# BMS.net
KiCad netlist of a schematic drawn in Altium Designer
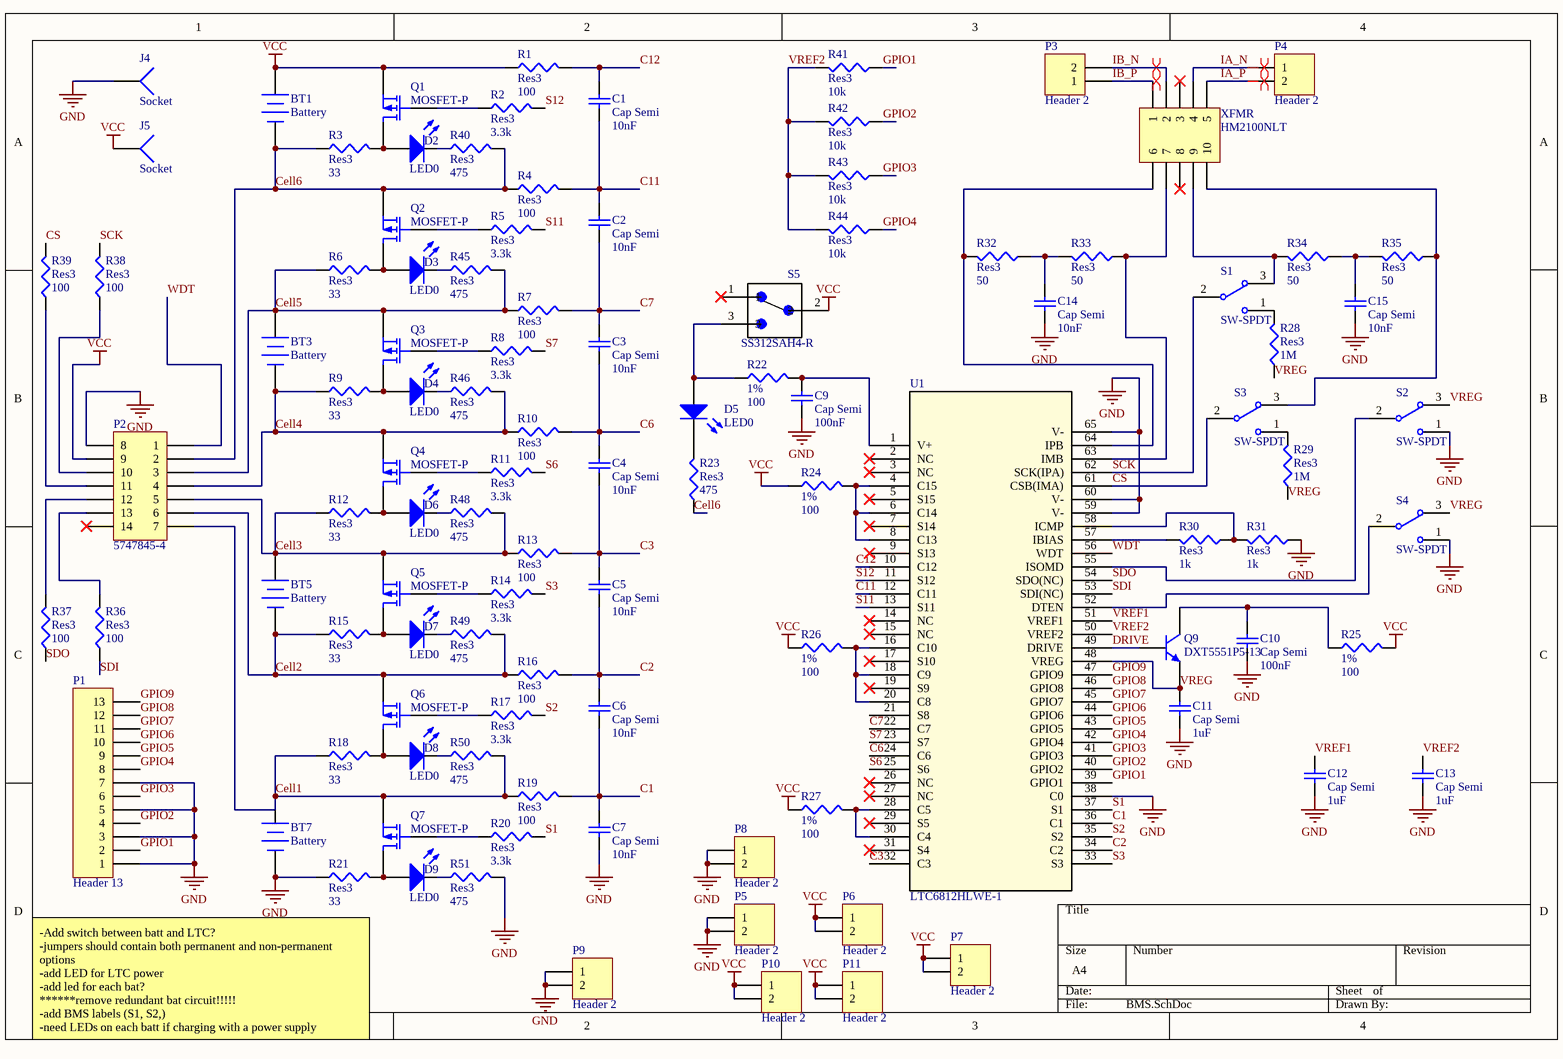
[diagram p0: BMS.SchDoc]

(export (version "E")
  (design (tool "Eeschema 10.0.6"))
  (components
    (comp (ref "BT1")
      (value "Battery")
      (footprint "18650 SMD:PCBComponent_1")
      (description "Multicell Battery")
      (fields (field (name "PUBLISHER") "Altium Limited"))
      (libsource (lib "Miscellaneous Devices") (part "Battery"))
    )
    (comp (ref "BT3")
      (value "Battery")
      (footprint "18650 SMD:PCBComponent_1")
      (description "Multicell Battery")
      (fields (field (name "PUBLISHER") "Altium Limited"))
      (libsource (lib "Miscellaneous Devices") (part "Battery"))
    )
    (comp (ref "BT5")
      (value "Battery")
      (footprint "18650 SMD:PCBComponent_1")
      (description "Multicell Battery")
      (fields (field (name "PUBLISHER") "Altium Limited"))
      (libsource (lib "Miscellaneous Devices") (part "Battery"))
    )
    (comp (ref "BT7")
      (value "Battery")
      (footprint "18650 SMD:PCBComponent_1")
      (description "Multicell Battery")
      (fields (field (name "PUBLISHER") "Altium Limited"))
      (libsource (lib "Miscellaneous Devices") (part "Battery"))
    )
    (comp (ref "C1")
      (value "Cap Semi")
      (footprint "1608[0603]")
      (description "Capacitor (Semiconductor SIM Model)")
      (fields (field (name "ALTIUM_VALUE") "10nF") (field (name "PUBLISHER") "Altium Limited"))
      (libsource (lib "Miscellaneous Devices") (part "Cap Semi"))
    )
    (comp (ref "C2")
      (value "Cap Semi")
      (footprint "1608[0603]")
      (description "Capacitor (Semiconductor SIM Model)")
      (fields (field (name "ALTIUM_VALUE") "10nF") (field (name "PUBLISHER") "Altium Limited"))
      (libsource (lib "Miscellaneous Devices") (part "Cap Semi"))
    )
    (comp (ref "C3")
      (value "Cap Semi")
      (footprint "1608[0603]")
      (description "Capacitor (Semiconductor SIM Model)")
      (fields (field (name "ALTIUM_VALUE") "10nF") (field (name "PUBLISHER") "Altium Limited"))
      (libsource (lib "Miscellaneous Devices") (part "Cap Semi"))
    )
    (comp (ref "C4")
      (value "Cap Semi")
      (footprint "1608[0603]")
      (description "Capacitor (Semiconductor SIM Model)")
      (fields (field (name "ALTIUM_VALUE") "10nF") (field (name "PUBLISHER") "Altium Limited"))
      (libsource (lib "Miscellaneous Devices") (part "Cap Semi"))
    )
    (comp (ref "C5")
      (value "Cap Semi")
      (footprint "1608[0603]")
      (description "Capacitor (Semiconductor SIM Model)")
      (fields (field (name "ALTIUM_VALUE") "10nF") (field (name "PUBLISHER") "Altium Limited"))
      (libsource (lib "Miscellaneous Devices") (part "Cap Semi"))
    )
    (comp (ref "C6")
      (value "Cap Semi")
      (footprint "1608[0603]")
      (description "Capacitor (Semiconductor SIM Model)")
      (fields (field (name "ALTIUM_VALUE") "10nF") (field (name "PUBLISHER") "Altium Limited"))
      (libsource (lib "Miscellaneous Devices") (part "Cap Semi"))
    )
    (comp (ref "C7")
      (value "Cap Semi")
      (footprint "1608[0603]")
      (description "Capacitor (Semiconductor SIM Model)")
      (fields (field (name "ALTIUM_VALUE") "10nF") (field (name "PUBLISHER") "Altium Limited"))
      (libsource (lib "Miscellaneous Devices") (part "Cap Semi"))
    )
    (comp (ref "C9")
      (value "Cap Semi")
      (footprint "6-0805_N")
      (description "Capacitor (Semiconductor SIM Model)")
      (fields (field (name "ALTIUM_VALUE") "100nF") (field (name "PUBLISHER") "Altium Limited"))
      (libsource (lib "Miscellaneous Devices") (part "Cap Semi"))
    )
    (comp (ref "C10")
      (value "Cap Semi")
      (footprint "6-0805_N")
      (description "Capacitor (Semiconductor SIM Model)")
      (fields (field (name "ALTIUM_VALUE") "100nF") (field (name "PUBLISHER") "Altium Limited"))
      (libsource (lib "Miscellaneous Devices") (part "Cap Semi"))
    )
    (comp (ref "C11")
      (value "Cap Semi")
      (footprint "6-0805_N")
      (description "Capacitor (Semiconductor SIM Model)")
      (fields (field (name "ALTIUM_VALUE") "1uF") (field (name "PUBLISHER") "Altium Limited"))
      (libsource (lib "Miscellaneous Devices") (part "Cap Semi"))
    )
    (comp (ref "C12")
      (value "Cap Semi")
      (footprint "6-0805_N")
      (description "Capacitor (Semiconductor SIM Model)")
      (fields (field (name "ALTIUM_VALUE") "1uF") (field (name "PUBLISHER") "Altium Limited"))
      (libsource (lib "Miscellaneous Devices") (part "Cap Semi"))
    )
    (comp (ref "C13")
      (value "Cap Semi")
      (footprint "6-0805_N")
      (description "Capacitor (Semiconductor SIM Model)")
      (fields (field (name "ALTIUM_VALUE") "1uF") (field (name "PUBLISHER") "Altium Limited"))
      (libsource (lib "Miscellaneous Devices") (part "Cap Semi"))
    )
    (comp (ref "C14")
      (value "Cap Semi")
      (footprint "1608[0603]")
      (description "Capacitor (Semiconductor SIM Model)")
      (fields (field (name "ALTIUM_VALUE") "10nF") (field (name "PUBLISHER") "Altium Limited"))
      (libsource (lib "Miscellaneous Devices") (part "Cap Semi"))
    )
    (comp (ref "C15")
      (value "Cap Semi")
      (footprint "1608[0603]")
      (description "Capacitor (Semiconductor SIM Model)")
      (fields (field (name "ALTIUM_VALUE") "10nF") (field (name "PUBLISHER") "Altium Limited"))
      (libsource (lib "Miscellaneous Devices") (part "Cap Semi"))
    )
    (comp (ref "D2")
      (value "LED0")
      (footprint "J1-0603")
      (description "Typical INFRARED GaAs LED")
      (fields (field (name "PUBLISHER") "Altium Limited"))
      (libsource (lib "Miscellaneous Devices") (part "LED0"))
    )
    (comp (ref "D3")
      (value "LED0")
      (footprint "J1-0603")
      (description "Typical INFRARED GaAs LED")
      (fields (field (name "PUBLISHER") "Altium Limited"))
      (libsource (lib "Miscellaneous Devices") (part "LED0"))
    )
    (comp (ref "D4")
      (value "LED0")
      (footprint "J1-0603")
      (description "Typical INFRARED GaAs LED")
      (fields (field (name "PUBLISHER") "Altium Limited"))
      (libsource (lib "Miscellaneous Devices") (part "LED0"))
    )
    (comp (ref "D5")
      (value "LED0")
      (footprint "J1-0603")
      (description "Typical INFRARED GaAs LED")
      (fields (field (name "PUBLISHER") "Altium Limited"))
      (libsource (lib "Miscellaneous Devices") (part "LED0"))
    )
    (comp (ref "D6")
      (value "LED0")
      (footprint "J1-0603")
      (description "Typical INFRARED GaAs LED")
      (fields (field (name "PUBLISHER") "Altium Limited"))
      (libsource (lib "Miscellaneous Devices") (part "LED0"))
    )
    (comp (ref "D7")
      (value "LED0")
      (footprint "J1-0603")
      (description "Typical INFRARED GaAs LED")
      (fields (field (name "PUBLISHER") "Altium Limited"))
      (libsource (lib "Miscellaneous Devices") (part "LED0"))
    )
    (comp (ref "D8")
      (value "LED0")
      (footprint "J1-0603")
      (description "Typical INFRARED GaAs LED")
      (fields (field (name "PUBLISHER") "Altium Limited"))
      (libsource (lib "Miscellaneous Devices") (part "LED0"))
    )
    (comp (ref "D9")
      (value "LED0")
      (footprint "J1-0603")
      (description "Typical INFRARED GaAs LED")
      (fields (field (name "PUBLISHER") "Altium Limited"))
      (libsource (lib "Miscellaneous Devices") (part "LED0"))
    )
    (comp (ref "J4")
      (value "Socket")
      (footprint "SMD Power Pad:PCBComponent_1")
      (fields (field (name "PUBLISHER") "Altium Limited"))
      (libsource (lib "Miscellaneous Connectors") (part "Socket"))
    )
    (comp (ref "J5")
      (value "Socket")
      (footprint "SMD Power Pad:PCBComponent_1")
      (fields (field (name "PUBLISHER") "Altium Limited"))
      (libsource (lib "Miscellaneous Connectors") (part "Socket"))
    )
    (comp (ref "P1")
      (value "Header 13")
      (footprint "SMD Finger Pads:PCBComponent_1")
      (description "Header, 13-Pin")
      (fields (field (name "PUBLISHER") "Altium Limited"))
      (libsource (lib "Miscellaneous Connectors") (part "Header 13"))
    )
    (comp (ref "P2")
      (value "5747845-4")
      (footprint "*5747845-4")
      (description "Header, 7-Pin, Dual row")
      (fields (field (name "PUBLISHER") "Altium Limited"))
      (libsource (lib "Miscellaneous Connectors") (part "Header 7X2A"))
    )
    (comp (ref "P3")
      (value "Header 2")
      (footprint "Molex Connectors:WM4900-ND")
      (description "Header, 2-Pin")
      (fields (field (name "PUBLISHER") "Altium Limited"))
      (libsource (lib "") (part "Header 2_1"))
    )
    (comp (ref "P4")
      (value "Header 2")
      (footprint "Molex Connectors:WM4900-ND")
      (description "Header, 2-Pin")
      (fields (field (name "PUBLISHER") "Altium Limited"))
      (libsource (lib "Miscellaneous Connectors") (part "Header 2"))
    )
    (comp (ref "P5")
      (value "Header 2")
      (footprint "5104:PCBComponent_1")
      (description "Header, 2-Pin")
      (fields (field (name "PUBLISHER") "Altium Limited"))
      (libsource (lib "Miscellaneous Connectors") (part "Header 2"))
    )
    (comp (ref "P6")
      (value "Header 2")
      (footprint "5104:PCBComponent_1")
      (description "Header, 2-Pin")
      (fields (field (name "PUBLISHER") "Altium Limited"))
      (libsource (lib "Miscellaneous Connectors") (part "Header 2"))
    )
    (comp (ref "P7")
      (value "Header 2")
      (footprint "5104:PCBComponent_1")
      (description "Header, 2-Pin")
      (fields (field (name "PUBLISHER") "Altium Limited"))
      (libsource (lib "Miscellaneous Connectors") (part "Header 2"))
    )
    (comp (ref "P8")
      (value "Header 2")
      (footprint "5104:PCBComponent_1")
      (description "Header, 2-Pin")
      (fields (field (name "PUBLISHER") "Altium Limited"))
      (libsource (lib "Miscellaneous Connectors") (part "Header 2"))
    )
    (comp (ref "P9")
      (value "Header 2")
      (footprint "5104:PCBComponent_1")
      (description "Header, 2-Pin")
      (fields (field (name "PUBLISHER") "Altium Limited"))
      (libsource (lib "Miscellaneous Connectors") (part "Header 2"))
    )
    (comp (ref "P10")
      (value "Header 2")
      (footprint "5104:PCBComponent_1")
      (description "Header, 2-Pin")
      (fields (field (name "PUBLISHER") "Altium Limited"))
      (libsource (lib "Miscellaneous Connectors") (part "Header 2"))
    )
    (comp (ref "P11")
      (value "Header 2")
      (footprint "5104:PCBComponent_1")
      (description "Header, 2-Pin")
      (fields (field (name "PUBLISHER") "Altium Limited"))
      (libsource (lib "Miscellaneous Connectors") (part "Header 2"))
    )
    (comp (ref "Q1")
      (value "MOSFET-P")
      (footprint "SOT95P245X110-3N")
      (description "P-Channel MOSFET")
      (fields (field (name "PUBLISHER") "Altium Limited"))
      (libsource (lib "Miscellaneous Devices") (part "MOSFET-P"))
    )
    (comp (ref "Q2")
      (value "MOSFET-P")
      (footprint "SOT95P245X110-3N")
      (description "P-Channel MOSFET")
      (fields (field (name "PUBLISHER") "Altium Limited"))
      (libsource (lib "Miscellaneous Devices") (part "MOSFET-P"))
    )
    (comp (ref "Q3")
      (value "MOSFET-P")
      (footprint "SOT95P245X110-3N")
      (description "P-Channel MOSFET")
      (fields (field (name "PUBLISHER") "Altium Limited"))
      (libsource (lib "Miscellaneous Devices") (part "MOSFET-P"))
    )
    (comp (ref "Q4")
      (value "MOSFET-P")
      (footprint "SOT95P245X110-3N")
      (description "P-Channel MOSFET")
      (fields (field (name "PUBLISHER") "Altium Limited"))
      (libsource (lib "Miscellaneous Devices") (part "MOSFET-P"))
    )
    (comp (ref "Q5")
      (value "MOSFET-P")
      (footprint "SOT95P245X110-3N")
      (description "P-Channel MOSFET")
      (fields (field (name "PUBLISHER") "Altium Limited"))
      (libsource (lib "Miscellaneous Devices") (part "MOSFET-P"))
    )
    (comp (ref "Q6")
      (value "MOSFET-P")
      (footprint "SOT95P245X110-3N")
      (description "P-Channel MOSFET")
      (fields (field (name "PUBLISHER") "Altium Limited"))
      (libsource (lib "Miscellaneous Devices") (part "MOSFET-P"))
    )
    (comp (ref "Q7")
      (value "MOSFET-P")
      (footprint "SOT95P245X110-3N")
      (description "P-Channel MOSFET")
      (fields (field (name "PUBLISHER") "Altium Limited"))
      (libsource (lib "Miscellaneous Devices") (part "MOSFET-P"))
    )
    (comp (ref "Q9")
      (value "DXT5551P5-13")
      (footprint "DXT5551P5-13")
      (description "NPN General Purpose Amplifier")
      (fields (field (name "PUBLISHER") "Altium Limited"))
      (libsource (lib "Miscellaneous Devices") (part "2N3904"))
    )
    (comp (ref "R1")
      (value "Res3")
      (footprint "J1-0603")
      (description "Resistor")
      (fields (field (name "ALTIUM_VALUE") "100") (field (name "PUBLISHER") "Altium Limited"))
      (libsource (lib "Miscellaneous Devices") (part "Res3"))
    )
    (comp (ref "R2")
      (value "Res3")
      (footprint "J1-0603")
      (description "Resistor")
      (fields (field (name "ALTIUM_VALUE") "3.3k") (field (name "PUBLISHER") "Altium Limited"))
      (libsource (lib "Miscellaneous Devices") (part "Res3"))
    )
    (comp (ref "R3")
      (value "Res3")
      (footprint "12Z-2010")
      (description "Resistor")
      (fields (field (name "ALTIUM_VALUE") "33") (field (name "PUBLISHER") "Altium Limited"))
      (libsource (lib "Miscellaneous Devices") (part "Res3"))
    )
    (comp (ref "R4")
      (value "Res3")
      (footprint "J1-0603")
      (description "Resistor")
      (fields (field (name "ALTIUM_VALUE") "100") (field (name "PUBLISHER") "Altium Limited"))
      (libsource (lib "Miscellaneous Devices") (part "Res3"))
    )
    (comp (ref "R5")
      (value "Res3")
      (footprint "J1-0603")
      (description "Resistor")
      (fields (field (name "ALTIUM_VALUE") "3.3k") (field (name "PUBLISHER") "Altium Limited"))
      (libsource (lib "Miscellaneous Devices") (part "Res3"))
    )
    (comp (ref "R6")
      (value "Res3")
      (footprint "12Z-2010")
      (description "Resistor")
      (fields (field (name "ALTIUM_VALUE") "33") (field (name "PUBLISHER") "Altium Limited"))
      (libsource (lib "Miscellaneous Devices") (part "Res3"))
    )
    (comp (ref "R7")
      (value "Res3")
      (footprint "J1-0603")
      (description "Resistor")
      (fields (field (name "ALTIUM_VALUE") "100") (field (name "PUBLISHER") "Altium Limited"))
      (libsource (lib "Miscellaneous Devices") (part "Res3"))
    )
    (comp (ref "R8")
      (value "Res3")
      (footprint "J1-0603")
      (description "Resistor")
      (fields (field (name "ALTIUM_VALUE") "3.3k") (field (name "PUBLISHER") "Altium Limited"))
      (libsource (lib "Miscellaneous Devices") (part "Res3"))
    )
    (comp (ref "R9")
      (value "Res3")
      (footprint "12Z-2010")
      (description "Resistor")
      (fields (field (name "ALTIUM_VALUE") "33") (field (name "PUBLISHER") "Altium Limited"))
      (libsource (lib "Miscellaneous Devices") (part "Res3"))
    )
    (comp (ref "R10")
      (value "Res3")
      (footprint "J1-0603")
      (description "Resistor")
      (fields (field (name "ALTIUM_VALUE") "100") (field (name "PUBLISHER") "Altium Limited"))
      (libsource (lib "Miscellaneous Devices") (part "Res3"))
    )
    (comp (ref "R11")
      (value "Res3")
      (footprint "J1-0603")
      (description "Resistor")
      (fields (field (name "ALTIUM_VALUE") "3.3k") (field (name "PUBLISHER") "Altium Limited"))
      (libsource (lib "Miscellaneous Devices") (part "Res3"))
    )
    (comp (ref "R12")
      (value "Res3")
      (footprint "12Z-2010")
      (description "Resistor")
      (fields (field (name "ALTIUM_VALUE") "33") (field (name "PUBLISHER") "Altium Limited"))
      (libsource (lib "Miscellaneous Devices") (part "Res3"))
    )
    (comp (ref "R13")
      (value "Res3")
      (footprint "J1-0603")
      (description "Resistor")
      (fields (field (name "ALTIUM_VALUE") "100") (field (name "PUBLISHER") "Altium Limited"))
      (libsource (lib "Miscellaneous Devices") (part "Res3"))
    )
    (comp (ref "R14")
      (value "Res3")
      (footprint "J1-0603")
      (description "Resistor")
      (fields (field (name "ALTIUM_VALUE") "3.3k") (field (name "PUBLISHER") "Altium Limited"))
      (libsource (lib "Miscellaneous Devices") (part "Res3"))
    )
    (comp (ref "R15")
      (value "Res3")
      (footprint "12Z-2010")
      (description "Resistor")
      (fields (field (name "ALTIUM_VALUE") "33") (field (name "PUBLISHER") "Altium Limited"))
      (libsource (lib "Miscellaneous Devices") (part "Res3"))
    )
    (comp (ref "R16")
      (value "Res3")
      (footprint "J1-0603")
      (description "Resistor")
      (fields (field (name "ALTIUM_VALUE") "100") (field (name "PUBLISHER") "Altium Limited"))
      (libsource (lib "Miscellaneous Devices") (part "Res3"))
    )
    (comp (ref "R17")
      (value "Res3")
      (footprint "J1-0603")
      (description "Resistor")
      (fields (field (name "ALTIUM_VALUE") "3.3k") (field (name "PUBLISHER") "Altium Limited"))
      (libsource (lib "Miscellaneous Devices") (part "Res3"))
    )
    (comp (ref "R18")
      (value "Res3")
      (footprint "12Z-2010")
      (description "Resistor")
      (fields (field (name "ALTIUM_VALUE") "33") (field (name "PUBLISHER") "Altium Limited"))
      (libsource (lib "Miscellaneous Devices") (part "Res3"))
    )
    (comp (ref "R19")
      (value "Res3")
      (footprint "J1-0603")
      (description "Resistor")
      (fields (field (name "ALTIUM_VALUE") "100") (field (name "PUBLISHER") "Altium Limited"))
      (libsource (lib "Miscellaneous Devices") (part "Res3"))
    )
    (comp (ref "R20")
      (value "Res3")
      (footprint "J1-0603")
      (description "Resistor")
      (fields (field (name "ALTIUM_VALUE") "3.3k") (field (name "PUBLISHER") "Altium Limited"))
      (libsource (lib "Miscellaneous Devices") (part "Res3"))
    )
    (comp (ref "R21")
      (value "Res3")
      (footprint "12Z-2010")
      (description "Resistor")
      (fields (field (name "ALTIUM_VALUE") "33") (field (name "PUBLISHER") "Altium Limited"))
      (libsource (lib "Miscellaneous Devices") (part "Res3"))
    )
    (comp (ref "R22")
      (value "1%")
      (footprint "J1-0603")
      (description "Resistor")
      (fields (field (name "ALTIUM_VALUE") "100") (field (name "PUBLISHER") "Altium Limited"))
      (libsource (lib "Miscellaneous Devices") (part "Res3"))
    )
    (comp (ref "R23")
      (value "Res3")
      (footprint "J1-0603")
      (description "Resistor")
      (fields (field (name "ALTIUM_VALUE") "475") (field (name "PUBLISHER") "Altium Limited"))
      (libsource (lib "Miscellaneous Devices") (part "Res3"))
    )
    (comp (ref "R24")
      (value "1%")
      (footprint "J1-0603")
      (description "Resistor")
      (fields (field (name "ALTIUM_VALUE") "100") (field (name "PUBLISHER") "Altium Limited"))
      (libsource (lib "Miscellaneous Devices") (part "Res3"))
    )
    (comp (ref "R25")
      (value "1%")
      (footprint "J1-0603")
      (description "Resistor")
      (fields (field (name "ALTIUM_VALUE") "100") (field (name "PUBLISHER") "Altium Limited"))
      (libsource (lib "Miscellaneous Devices") (part "Res3"))
    )
    (comp (ref "R26")
      (value "1%")
      (footprint "J1-0603")
      (description "Resistor")
      (fields (field (name "ALTIUM_VALUE") "100") (field (name "PUBLISHER") "Altium Limited"))
      (libsource (lib "Miscellaneous Devices") (part "Res3"))
    )
    (comp (ref "R27")
      (value "1%")
      (footprint "J1-0603")
      (description "Resistor")
      (fields (field (name "ALTIUM_VALUE") "100") (field (name "PUBLISHER") "Altium Limited"))
      (libsource (lib "Miscellaneous Devices") (part "Res3"))
    )
    (comp (ref "R28")
      (value "Res3")
      (footprint "J1-0603")
      (description "Resistor")
      (fields (field (name "ALTIUM_VALUE") "1M") (field (name "PUBLISHER") "Altium Limited"))
      (libsource (lib "Miscellaneous Devices") (part "Res3"))
    )
    (comp (ref "R29")
      (value "Res3")
      (footprint "J1-0603")
      (description "Resistor")
      (fields (field (name "ALTIUM_VALUE") "1M") (field (name "PUBLISHER") "Altium Limited"))
      (libsource (lib "Miscellaneous Devices") (part "Res3"))
    )
    (comp (ref "R30")
      (value "Res3")
      (footprint "J1-0603")
      (description "Resistor")
      (fields (field (name "ALTIUM_VALUE") "1k") (field (name "PUBLISHER") "Altium Limited"))
      (libsource (lib "Miscellaneous Devices") (part "Res3"))
    )
    (comp (ref "R31")
      (value "Res3")
      (footprint "J1-0603")
      (description "Resistor")
      (fields (field (name "ALTIUM_VALUE") "1k") (field (name "PUBLISHER") "Altium Limited"))
      (libsource (lib "Miscellaneous Devices") (part "Res3"))
    )
    (comp (ref "R32")
      (value "Res3")
      (footprint "J1-0603")
      (description "Resistor")
      (fields (field (name "ALTIUM_VALUE") "50") (field (name "PUBLISHER") "Altium Limited"))
      (libsource (lib "Miscellaneous Devices") (part "Res3"))
    )
    (comp (ref "R33")
      (value "Res3")
      (footprint "J1-0603")
      (description "Resistor")
      (fields (field (name "ALTIUM_VALUE") "50") (field (name "PUBLISHER") "Altium Limited"))
      (libsource (lib "Miscellaneous Devices") (part "Res3"))
    )
    (comp (ref "R34")
      (value "Res3")
      (footprint "J1-0603")
      (description "Resistor")
      (fields (field (name "ALTIUM_VALUE") "50") (field (name "PUBLISHER") "Altium Limited"))
      (libsource (lib "Miscellaneous Devices") (part "Res3"))
    )
    (comp (ref "R35")
      (value "Res3")
      (footprint "J1-0603")
      (description "Resistor")
      (fields (field (name "ALTIUM_VALUE") "50") (field (name "PUBLISHER") "Altium Limited"))
      (libsource (lib "Miscellaneous Devices") (part "Res3"))
    )
    (comp (ref "R36")
      (value "Res3")
      (footprint "J1-0603")
      (description "Resistor")
      (fields (field (name "ALTIUM_VALUE") "100") (field (name "PUBLISHER") "Altium Limited"))
      (libsource (lib "Miscellaneous Devices") (part "Res3"))
    )
    (comp (ref "R37")
      (value "Res3")
      (footprint "J1-0603")
      (description "Resistor")
      (fields (field (name "ALTIUM_VALUE") "100") (field (name "PUBLISHER") "Altium Limited"))
      (libsource (lib "Miscellaneous Devices") (part "Res3"))
    )
    (comp (ref "R38")
      (value "Res3")
      (footprint "J1-0603")
      (description "Resistor")
      (fields (field (name "ALTIUM_VALUE") "100") (field (name "PUBLISHER") "Altium Limited"))
      (libsource (lib "Miscellaneous Devices") (part "Res3"))
    )
    (comp (ref "R39")
      (value "Res3")
      (footprint "J1-0603")
      (description "Resistor")
      (fields (field (name "ALTIUM_VALUE") "100") (field (name "PUBLISHER") "Altium Limited"))
      (libsource (lib "Miscellaneous Devices") (part "Res3"))
    )
    (comp (ref "R40")
      (value "Res3")
      (footprint "J1-0603")
      (description "Resistor")
      (fields (field (name "ALTIUM_VALUE") "475") (field (name "PUBLISHER") "Altium Limited"))
      (libsource (lib "Miscellaneous Devices") (part "Res3"))
    )
    (comp (ref "R41")
      (value "Res3")
      (footprint "J1-0603")
      (description "Resistor")
      (fields (field (name "ALTIUM_VALUE") "10k") (field (name "PUBLISHER") "Altium Limited"))
      (libsource (lib "Miscellaneous Devices") (part "Res3"))
    )
    (comp (ref "R42")
      (value "Res3")
      (footprint "J1-0603")
      (description "Resistor")
      (fields (field (name "ALTIUM_VALUE") "10k") (field (name "PUBLISHER") "Altium Limited"))
      (libsource (lib "Miscellaneous Devices") (part "Res3"))
    )
    (comp (ref "R43")
      (value "Res3")
      (footprint "J1-0603")
      (description "Resistor")
      (fields (field (name "ALTIUM_VALUE") "10k") (field (name "PUBLISHER") "Altium Limited"))
      (libsource (lib "Miscellaneous Devices") (part "Res3"))
    )
    (comp (ref "R44")
      (value "Res3")
      (footprint "J1-0603")
      (description "Resistor")
      (fields (field (name "ALTIUM_VALUE") "10k") (field (name "PUBLISHER") "Altium Limited"))
      (libsource (lib "Miscellaneous Devices") (part "Res3"))
    )
    (comp (ref "R45")
      (value "Res3")
      (footprint "J1-0603")
      (description "Resistor")
      (fields (field (name "ALTIUM_VALUE") "475") (field (name "PUBLISHER") "Altium Limited"))
      (libsource (lib "Miscellaneous Devices") (part "Res3"))
    )
    (comp (ref "R46")
      (value "Res3")
      (footprint "J1-0603")
      (description "Resistor")
      (fields (field (name "ALTIUM_VALUE") "475") (field (name "PUBLISHER") "Altium Limited"))
      (libsource (lib "Miscellaneous Devices") (part "Res3"))
    )
    (comp (ref "R48")
      (value "Res3")
      (footprint "J1-0603")
      (description "Resistor")
      (fields (field (name "ALTIUM_VALUE") "475") (field (name "PUBLISHER") "Altium Limited"))
      (libsource (lib "Miscellaneous Devices") (part "Res3"))
    )
    (comp (ref "R49")
      (value "Res3")
      (footprint "J1-0603")
      (description "Resistor")
      (fields (field (name "ALTIUM_VALUE") "475") (field (name "PUBLISHER") "Altium Limited"))
      (libsource (lib "Miscellaneous Devices") (part "Res3"))
    )
    (comp (ref "R50")
      (value "Res3")
      (footprint "J1-0603")
      (description "Resistor")
      (fields (field (name "ALTIUM_VALUE") "475") (field (name "PUBLISHER") "Altium Limited"))
      (libsource (lib "Miscellaneous Devices") (part "Res3"))
    )
    (comp (ref "R51")
      (value "Res3")
      (footprint "J1-0603")
      (description "Resistor")
      (fields (field (name "ALTIUM_VALUE") "475") (field (name "PUBLISHER") "Altium Limited"))
      (libsource (lib "Miscellaneous Devices") (part "Res3"))
    )
    (comp (ref "S1")
      (value "SW-SPDT")
      (footprint "*TSM-103-01-L-SV")
      (description "SPDT Subminiature Toggle Switch, Right Angle Mounting, Vertical Actuation")
      (fields (field (name "PUBLISHER") "Altium Limited"))
      (libsource (lib "Miscellaneous Devices") (part "SW-SPDT"))
    )
    (comp (ref "S2")
      (value "SW-SPDT")
      (footprint "*TSM-103-01-L-SV")
      (description "SPDT Subminiature Toggle Switch, Right Angle Mounting, Vertical Actuation")
      (fields (field (name "PUBLISHER") "Altium Limited"))
      (libsource (lib "Miscellaneous Devices") (part "SW-SPDT"))
    )
    (comp (ref "S3")
      (value "SW-SPDT")
      (footprint "*TSM-103-01-L-SV")
      (description "SPDT Subminiature Toggle Switch, Right Angle Mounting, Vertical Actuation")
      (fields (field (name "PUBLISHER") "Altium Limited"))
      (libsource (lib "Miscellaneous Devices") (part "SW-SPDT"))
    )
    (comp (ref "S4")
      (value "SW-SPDT")
      (footprint "*TSM-103-01-L-SV")
      (description "SPDT Subminiature Toggle Switch, Right Angle Mounting, Vertical Actuation")
      (fields (field (name "PUBLISHER") "Altium Limited"))
      (libsource (lib "Miscellaneous Devices") (part "SW-SPDT"))
    )
    (comp (ref "S5")
      (value "SS312SAH4-R")
      (footprint "*SW_SS312SAH4-R")
      (description "Switch Slide ON None ON SPDT Side Slide 0.1A 28VAC 28VDC 0.4VA 10000Cycles Gull Wing SMD T/R")
      (fields (field (name "MF") "NKK Switches"))
      (libsource (lib "SS312SAH4-R") (part "SS312SAH4-R"))
    )
    (comp (ref "U1")
      (value "LTC6812HLWE-1")
      (footprint "LQFP64_LWE_A - duplicate")
      (description "No Description Available")
      (fields (field (name "COPYRIGHT") "Copyright (C) 2018 Accelerated Designs. All rights reserved"))
      (libsource (lib "LTC6812") (part "LTC6812HLWE-1"))
    )
    (comp (ref "XFMR")
      (value "HM2100NLT")
      (footprint "HM2100NLT")
      (description "Header, 5-Pin, Dual row")
      (fields (field (name "PUBLISHER") "Altium Limited"))
      (libsource (lib "Miscellaneous Connectors") (part "Header 5X2A"))
    )
  )
  (nets
    (net (code "1") (name "/C1") (class "Default")
      (node (ref "C6") (pin "1") (pinfunction "1_1") (pintype "passive"))
      (node (ref "C7") (pin "2") (pinfunction "2_2") (pintype "passive"))
      (node (ref "R19") (pin "2") (pinfunction "2_2") (pintype "passive"))
      (node (ref "U1") (pin "36") (pinfunction "C1_36") (pintype "passive"))
    )
    (net (code "2") (name "/C2") (class "Default")
      (node (ref "C5") (pin "1") (pinfunction "1_1") (pintype "passive"))
      (node (ref "C6") (pin "2") (pinfunction "2_2") (pintype "passive"))
      (node (ref "R16") (pin "2") (pinfunction "2_2") (pintype "passive"))
      (node (ref "U1") (pin "34") (pinfunction "C2_34") (pintype "passive"))
    )
    (net (code "3") (name "/C3") (class "Default")
      (node (ref "C4") (pin "1") (pinfunction "1_1") (pintype "passive"))
      (node (ref "C5") (pin "2") (pinfunction "2_2") (pintype "passive"))
      (node (ref "R13") (pin "2") (pinfunction "2_2") (pintype "passive"))
      (node (ref "U1") (pin "32") (pinfunction "C3_32") (pintype "passive"))
    )
    (net (code "4") (name "/C6") (class "Default")
      (node (ref "C3") (pin "1") (pinfunction "1_1") (pintype "passive"))
      (node (ref "C4") (pin "2") (pinfunction "2_2") (pintype "passive"))
      (node (ref "R10") (pin "2") (pinfunction "2_2") (pintype "passive"))
      (node (ref "U1") (pin "24") (pinfunction "C6_24") (pintype "passive"))
    )
    (net (code "5") (name "/C7") (class "Default")
      (node (ref "C2") (pin "1") (pinfunction "1_1") (pintype "passive"))
      (node (ref "C3") (pin "2") (pinfunction "2_2") (pintype "passive"))
      (node (ref "R7") (pin "2") (pinfunction "2_2") (pintype "passive"))
      (node (ref "U1") (pin "22") (pinfunction "C7_22") (pintype "passive"))
    )
    (net (code "6") (name "/C11") (class "Default")
      (node (ref "C1") (pin "1") (pinfunction "1_1") (pintype "passive"))
      (node (ref "C2") (pin "2") (pinfunction "2_2") (pintype "passive"))
      (node (ref "R4") (pin "2") (pinfunction "2_2") (pintype "passive"))
      (node (ref "U1") (pin "12") (pinfunction "C11_12") (pintype "passive"))
    )
    (net (code "7") (name "/C12") (class "Default")
      (node (ref "C1") (pin "2") (pinfunction "2_2") (pintype "passive"))
      (node (ref "R1") (pin "2") (pinfunction "2_2") (pintype "passive"))
      (node (ref "U1") (pin "10") (pinfunction "C12_10") (pintype "passive"))
    )
    (net (code "8") (name "/CS") (class "Default")
      (node (ref "R39") (pin "1") (pinfunction "1_1") (pintype "passive"))
      (node (ref "S3") (pin "2") (pinfunction "2_2") (pintype "passive"))
      (node (ref "U1") (pin "61") (pinfunction "CSB(IMA)_61") (pintype "passive"))
    )
    (net (code "9") (name "/Cell1") (class "Default")
      (node (ref "BT7") (pin "1") (pinfunction "+_1") (pintype "passive"))
      (node (ref "P2") (pin "7") (pinfunction "7_7") (pintype "passive"))
      (node (ref "Q7") (pin "3") (pinfunction "S_3") (pintype "passive"))
      (node (ref "R18") (pin "2") (pinfunction "2_2") (pintype "passive"))
      (node (ref "R19") (pin "1") (pinfunction "1_1") (pintype "passive"))
      (node (ref "R50") (pin "1") (pinfunction "1_1") (pintype "passive"))
    )
    (net (code "10") (name "/Cell2") (class "Default")
      (node (ref "BT5") (pin "2") (pinfunction "-_2") (pintype "passive"))
      (node (ref "P2") (pin "6") (pinfunction "6_6") (pintype "passive"))
      (node (ref "Q6") (pin "3") (pinfunction "S_3") (pintype "passive"))
      (node (ref "R15") (pin "2") (pinfunction "2_2") (pintype "passive"))
      (node (ref "R16") (pin "1") (pinfunction "1_1") (pintype "passive"))
      (node (ref "R49") (pin "1") (pinfunction "1_1") (pintype "passive"))
    )
    (net (code "11") (name "/Cell3") (class "Default")
      (node (ref "BT5") (pin "1") (pinfunction "+_1") (pintype "passive"))
      (node (ref "P2") (pin "5") (pinfunction "5_5") (pintype "passive"))
      (node (ref "Q5") (pin "3") (pinfunction "S_3") (pintype "passive"))
      (node (ref "R12") (pin "2") (pinfunction "2_2") (pintype "passive"))
      (node (ref "R13") (pin "1") (pinfunction "1_1") (pintype "passive"))
      (node (ref "R48") (pin "1") (pinfunction "1_1") (pintype "passive"))
    )
    (net (code "12") (name "/Cell4") (class "Default")
      (node (ref "BT3") (pin "2") (pinfunction "-_2") (pintype "passive"))
      (node (ref "P2") (pin "4") (pinfunction "4_4") (pintype "passive"))
      (node (ref "Q4") (pin "3") (pinfunction "S_3") (pintype "passive"))
      (node (ref "R10") (pin "1") (pinfunction "1_1") (pintype "passive"))
      (node (ref "R46") (pin "1") (pinfunction "1_1") (pintype "passive"))
      (node (ref "R9") (pin "2") (pinfunction "2_2") (pintype "passive"))
    )
    (net (code "13") (name "/Cell5") (class "Default")
      (node (ref "BT3") (pin "1") (pinfunction "+_1") (pintype "passive"))
      (node (ref "P2") (pin "3") (pinfunction "3_3") (pintype "passive"))
      (node (ref "Q3") (pin "3") (pinfunction "S_3") (pintype "passive"))
      (node (ref "R45") (pin "1") (pinfunction "1_1") (pintype "passive"))
      (node (ref "R6") (pin "2") (pinfunction "2_2") (pintype "passive"))
      (node (ref "R7") (pin "1") (pinfunction "1_1") (pintype "passive"))
    )
    (net (code "14") (name "/Cell6") (class "Default")
      (node (ref "BT1") (pin "2") (pinfunction "-_2") (pintype "passive"))
      (node (ref "P2") (pin "2") (pinfunction "2_2") (pintype "passive"))
      (node (ref "Q2") (pin "3") (pinfunction "S_3") (pintype "passive"))
      (node (ref "R23") (pin "2") (pinfunction "2_2") (pintype "passive"))
      (node (ref "R3") (pin "2") (pinfunction "2_2") (pintype "passive"))
      (node (ref "R4") (pin "1") (pinfunction "1_1") (pintype "passive"))
      (node (ref "R40") (pin "1") (pinfunction "1_1") (pintype "passive"))
    )
    (net (code "15") (name "/DRIVE") (class "Default")
      (node (ref "Q9") (pin "2") (pinfunction "B_2") (pintype "passive"))
      (node (ref "U1") (pin "49") (pinfunction "DRIVE_49") (pintype "passive"))
    )
    (net (code "16") (name "/GPIO1") (class "Default")
      (node (ref "P1") (pin "2") (pinfunction "2_2") (pintype "passive"))
      (node (ref "R41") (pin "2") (pinfunction "2_2") (pintype "passive"))
      (node (ref "U1") (pin "39") (pinfunction "GPIO1_39") (pintype "passive"))
    )
    (net (code "17") (name "/GPIO2") (class "Default")
      (node (ref "P1") (pin "4") (pinfunction "4_4") (pintype "passive"))
      (node (ref "R42") (pin "2") (pinfunction "2_2") (pintype "passive"))
      (node (ref "U1") (pin "40") (pinfunction "GPIO2_40") (pintype "passive"))
    )
    (net (code "18") (name "/GPIO3") (class "Default")
      (node (ref "P1") (pin "6") (pinfunction "6_6") (pintype "passive"))
      (node (ref "R43") (pin "2") (pinfunction "2_2") (pintype "passive"))
      (node (ref "U1") (pin "41") (pinfunction "GPIO3_41") (pintype "passive"))
    )
    (net (code "19") (name "/GPIO4") (class "Default")
      (node (ref "P1") (pin "8") (pinfunction "8_8") (pintype "passive"))
      (node (ref "R44") (pin "2") (pinfunction "2_2") (pintype "passive"))
      (node (ref "U1") (pin "42") (pinfunction "GPIO4_42") (pintype "passive"))
    )
    (net (code "20") (name "/GPIO5") (class "Default")
      (node (ref "P1") (pin "9") (pinfunction "9_9") (pintype "passive"))
      (node (ref "U1") (pin "43") (pinfunction "GPIO5_43") (pintype "passive"))
    )
    (net (code "21") (name "/GPIO6") (class "Default")
      (node (ref "P1") (pin "10") (pinfunction "10_10") (pintype "passive"))
      (node (ref "U1") (pin "44") (pinfunction "GPIO6_44") (pintype "passive"))
    )
    (net (code "22") (name "/GPIO7") (class "Default")
      (node (ref "P1") (pin "11") (pinfunction "11_11") (pintype "passive"))
      (node (ref "U1") (pin "45") (pinfunction "GPIO7_45") (pintype "passive"))
    )
    (net (code "23") (name "/GPIO8") (class "Default")
      (node (ref "P1") (pin "12") (pinfunction "12_12") (pintype "passive"))
      (node (ref "U1") (pin "46") (pinfunction "GPIO8_46") (pintype "passive"))
    )
    (net (code "24") (name "/GPIO9") (class "Default")
      (node (ref "P1") (pin "13") (pinfunction "13_13") (pintype "passive"))
      (node (ref "U1") (pin "47") (pinfunction "GPIO9_47") (pintype "passive"))
    )
    (net (code "25") (name "/IA_N") (class "Default")
      (node (ref "P4") (pin "1") (pinfunction "1_1") (pintype "passive"))
      (node (ref "XFMR") (pin "4") (pinfunction "4_4") (pintype "passive"))
    )
    (net (code "26") (name "/IA_P") (class "Default")
      (node (ref "P4") (pin "2") (pinfunction "2_2") (pintype "passive"))
      (node (ref "XFMR") (pin "5") (pinfunction "5_5") (pintype "passive"))
    )
    (net (code "27") (name "/IB_N") (class "Default")
      (node (ref "P3") (pin "2") (pinfunction "2_2") (pintype "passive"))
      (node (ref "XFMR") (pin "2") (pinfunction "2_2") (pintype "passive"))
    )
    (net (code "28") (name "/IB_P") (class "Default")
      (node (ref "P3") (pin "1") (pinfunction "1_1") (pintype "passive"))
      (node (ref "XFMR") (pin "1") (pinfunction "1_1") (pintype "passive"))
    )
    (net (code "29") (name "/S1") (class "Default")
      (node (ref "R20") (pin "2") (pinfunction "2_2") (pintype "passive"))
      (node (ref "U1") (pin "37") (pinfunction "S1_37") (pintype "passive"))
    )
    (net (code "30") (name "/S2") (class "Default")
      (node (ref "R17") (pin "2") (pinfunction "2_2") (pintype "passive"))
      (node (ref "U1") (pin "35") (pinfunction "S2_35") (pintype "passive"))
    )
    (net (code "31") (name "/S3") (class "Default")
      (node (ref "R14") (pin "2") (pinfunction "2_2") (pintype "passive"))
      (node (ref "U1") (pin "33") (pinfunction "S3_33") (pintype "passive"))
    )
    (net (code "32") (name "/S6") (class "Default")
      (node (ref "R11") (pin "2") (pinfunction "2_2") (pintype "passive"))
      (node (ref "U1") (pin "25") (pinfunction "S6_25") (pintype "passive"))
    )
    (net (code "33") (name "/S7") (class "Default")
      (node (ref "R8") (pin "2") (pinfunction "2_2") (pintype "passive"))
      (node (ref "U1") (pin "23") (pinfunction "S7_23") (pintype "passive"))
    )
    (net (code "34") (name "/S11") (class "Default")
      (node (ref "R5") (pin "2") (pinfunction "2_2") (pintype "passive"))
      (node (ref "U1") (pin "13") (pinfunction "S11_13") (pintype "passive"))
    )
    (net (code "35") (name "/S12") (class "Default")
      (node (ref "R2") (pin "2") (pinfunction "2_2") (pintype "passive"))
      (node (ref "U1") (pin "11") (pinfunction "S12_11") (pintype "passive"))
    )
    (net (code "36") (name "/SCK") (class "Default")
      (node (ref "R38") (pin "1") (pinfunction "1_1") (pintype "passive"))
      (node (ref "S1") (pin "2") (pinfunction "2_2") (pintype "passive"))
      (node (ref "U1") (pin "62") (pinfunction "SCK(IPA)_62") (pintype "passive"))
    )
    (net (code "37") (name "/SDI") (class "Default")
      (node (ref "R36") (pin "2") (pinfunction "2_2") (pintype "passive"))
      (node (ref "U1") (pin "53") (pinfunction "SDI(NC)_53") (pintype "passive"))
    )
    (net (code "38") (name "/SDO") (class "Default")
      (node (ref "R37") (pin "2") (pinfunction "2_2") (pintype "passive"))
      (node (ref "U1") (pin "54") (pinfunction "SDO(NC)_54") (pintype "passive"))
    )
    (net (code "39") (name "/VREF1") (class "Default")
      (node (ref "C12") (pin "2") (pinfunction "2_2") (pintype "passive"))
      (node (ref "U1") (pin "51") (pinfunction "VREF1_51") (pintype "passive"))
    )
    (net (code "40") (name "/VREF2") (class "Default")
      (node (ref "C13") (pin "2") (pinfunction "2_2") (pintype "passive"))
      (node (ref "R41") (pin "1") (pinfunction "1_1") (pintype "passive"))
      (node (ref "R42") (pin "1") (pinfunction "1_1") (pintype "passive"))
      (node (ref "R43") (pin "1") (pinfunction "1_1") (pintype "passive"))
      (node (ref "R44") (pin "1") (pinfunction "1_1") (pintype "passive"))
      (node (ref "U1") (pin "50") (pinfunction "VREF2_50") (pintype "passive"))
    )
    (net (code "41") (name "/VREG") (class "Default")
      (node (ref "C11") (pin "2") (pinfunction "2_2") (pintype "passive"))
      (node (ref "Q9") (pin "1") (pinfunction "E_1") (pintype "passive"))
      (node (ref "R28") (pin "2") (pinfunction "2_2") (pintype "passive"))
      (node (ref "R29") (pin "2") (pinfunction "2_2") (pintype "passive"))
      (node (ref "S2") (pin "3") (pinfunction "3_3") (pintype "passive"))
      (node (ref "S4") (pin "3") (pinfunction "3_3") (pintype "passive"))
      (node (ref "U1") (pin "48") (pinfunction "VREG_48") (pintype "passive"))
    )
    (net (code "42") (name "/WDT") (class "Default")
      (node (ref "P2") (pin "1") (pinfunction "1_1") (pintype "passive"))
      (node (ref "U1") (pin "56") (pinfunction "WDT_56") (pintype "passive"))
    )
    (net (code "43") (name "GND") (class "Default")
      (node (ref "BT7") (pin "2") (pinfunction "-_2") (pintype "passive"))
      (node (ref "C10") (pin "1") (pinfunction "1_1") (pintype "passive"))
      (node (ref "C11") (pin "1") (pinfunction "1_1") (pintype "passive"))
      (node (ref "C12") (pin "1") (pinfunction "1_1") (pintype "passive"))
      (node (ref "C13") (pin "1") (pinfunction "1_1") (pintype "passive"))
      (node (ref "C14") (pin "1") (pinfunction "1_1") (pintype "passive"))
      (node (ref "C15") (pin "1") (pinfunction "1_1") (pintype "passive"))
      (node (ref "C7") (pin "1") (pinfunction "1_1") (pintype "passive"))
      (node (ref "C9") (pin "1") (pinfunction "1_1") (pintype "passive"))
      (node (ref "J4") (pin "1") (pinfunction "1_1") (pintype "passive"))
      (node (ref "P1") (pin "1") (pinfunction "1_1") (pintype "passive"))
      (node (ref "P1") (pin "3") (pinfunction "3_3") (pintype "passive"))
      (node (ref "P1") (pin "5") (pinfunction "5_5") (pintype "passive"))
      (node (ref "P1") (pin "7") (pinfunction "7_7") (pintype "passive"))
      (node (ref "P2") (pin "8") (pinfunction "8_8") (pintype "passive"))
      (node (ref "P5") (pin "1") (pinfunction "1_1") (pintype "passive"))
      (node (ref "P5") (pin "2") (pinfunction "2_2") (pintype "passive"))
      (node (ref "P8") (pin "1") (pinfunction "1_1") (pintype "passive"))
      (node (ref "P8") (pin "2") (pinfunction "2_2") (pintype "passive"))
      (node (ref "P9") (pin "1") (pinfunction "1_1") (pintype "passive"))
      (node (ref "P9") (pin "2") (pinfunction "2_2") (pintype "passive"))
      (node (ref "R21") (pin "2") (pinfunction "2_2") (pintype "passive"))
      (node (ref "R31") (pin "2") (pinfunction "2_2") (pintype "passive"))
      (node (ref "R51") (pin "1") (pinfunction "1_1") (pintype "passive"))
      (node (ref "S2") (pin "1") (pinfunction "1_1") (pintype "passive"))
      (node (ref "S4") (pin "1") (pinfunction "1_1") (pintype "passive"))
      (node (ref "U1") (pin "38") (pinfunction "C0_38") (pintype "passive"))
      (node (ref "U1") (pin "59") (pinfunction "V-_59") (pintype "passive"))
      (node (ref "U1") (pin "60") (pinfunction "V-_60") (pintype "passive"))
      (node (ref "U1") (pin "65") (pinfunction "V-_65") (pintype "passive"))
    )
    (net (code "44") (name "Net-(C14-Pad2)") (class "Default")
      (node (ref "C14") (pin "2") (pinfunction "2_2") (pintype "passive"))
      (node (ref "R32") (pin "2") (pinfunction "2_2") (pintype "passive"))
      (node (ref "R33") (pin "1") (pinfunction "1_1") (pintype "passive"))
    )
    (net (code "45") (name "Net-(C15-Pad2)") (class "Default")
      (node (ref "C15") (pin "2") (pinfunction "2_2") (pintype "passive"))
      (node (ref "R34") (pin "2") (pinfunction "2_2") (pintype "passive"))
      (node (ref "R35") (pin "1") (pinfunction "1_1") (pintype "passive"))
    )
    (net (code "46") (name "Net-(D2-A)") (class "Default")
      (node (ref "D2") (pin "1") (pinfunction "A_1") (pintype "passive"))
      (node (ref "Q1") (pin "1") (pinfunction "D_1") (pintype "passive"))
      (node (ref "R3") (pin "1") (pinfunction "1_1") (pintype "passive"))
    )
    (net (code "47") (name "Net-(D2-K)") (class "Default")
      (node (ref "D2") (pin "2") (pinfunction "K_2") (pintype "passive"))
      (node (ref "R40") (pin "2") (pinfunction "2_2") (pintype "passive"))
    )
    (net (code "48") (name "Net-(D3-A)") (class "Default")
      (node (ref "D3") (pin "1") (pinfunction "A_1") (pintype "passive"))
      (node (ref "Q2") (pin "1") (pinfunction "D_1") (pintype "passive"))
      (node (ref "R6") (pin "1") (pinfunction "1_1") (pintype "passive"))
    )
    (net (code "49") (name "Net-(D3-K)") (class "Default")
      (node (ref "D3") (pin "2") (pinfunction "K_2") (pintype "passive"))
      (node (ref "R45") (pin "2") (pinfunction "2_2") (pintype "passive"))
    )
    (net (code "50") (name "Net-(D4-A)") (class "Default")
      (node (ref "D4") (pin "1") (pinfunction "A_1") (pintype "passive"))
      (node (ref "Q3") (pin "1") (pinfunction "D_1") (pintype "passive"))
      (node (ref "R9") (pin "1") (pinfunction "1_1") (pintype "passive"))
    )
    (net (code "51") (name "Net-(D4-K)") (class "Default")
      (node (ref "D4") (pin "2") (pinfunction "K_2") (pintype "passive"))
      (node (ref "R46") (pin "2") (pinfunction "2_2") (pintype "passive"))
    )
    (net (code "52") (name "Net-(D5-A)") (class "Default")
      (node (ref "D5") (pin "1") (pinfunction "A_1") (pintype "passive"))
      (node (ref "R22") (pin "2") (pinfunction "2_2") (pintype "passive"))
      (node (ref "S5") (pin "3") (pinfunction "3_3") (pintype "passive"))
    )
    (net (code "53") (name "Net-(D5-K)") (class "Default")
      (node (ref "D5") (pin "2") (pinfunction "K_2") (pintype "passive"))
      (node (ref "R23") (pin "1") (pinfunction "1_1") (pintype "passive"))
    )
    (net (code "54") (name "Net-(D6-A)") (class "Default")
      (node (ref "D6") (pin "1") (pinfunction "A_1") (pintype "passive"))
      (node (ref "Q4") (pin "1") (pinfunction "D_1") (pintype "passive"))
      (node (ref "R12") (pin "1") (pinfunction "1_1") (pintype "passive"))
    )
    (net (code "55") (name "Net-(D6-K)") (class "Default")
      (node (ref "D6") (pin "2") (pinfunction "K_2") (pintype "passive"))
      (node (ref "R48") (pin "2") (pinfunction "2_2") (pintype "passive"))
    )
    (net (code "56") (name "Net-(D7-A)") (class "Default")
      (node (ref "D7") (pin "1") (pinfunction "A_1") (pintype "passive"))
      (node (ref "Q5") (pin "1") (pinfunction "D_1") (pintype "passive"))
      (node (ref "R15") (pin "1") (pinfunction "1_1") (pintype "passive"))
    )
    (net (code "57") (name "Net-(D7-K)") (class "Default")
      (node (ref "D7") (pin "2") (pinfunction "K_2") (pintype "passive"))
      (node (ref "R49") (pin "2") (pinfunction "2_2") (pintype "passive"))
    )
    (net (code "58") (name "Net-(D8-A)") (class "Default")
      (node (ref "D8") (pin "1") (pinfunction "A_1") (pintype "passive"))
      (node (ref "Q6") (pin "1") (pinfunction "D_1") (pintype "passive"))
      (node (ref "R18") (pin "1") (pinfunction "1_1") (pintype "passive"))
    )
    (net (code "59") (name "Net-(D8-K)") (class "Default")
      (node (ref "D8") (pin "2") (pinfunction "K_2") (pintype "passive"))
      (node (ref "R50") (pin "2") (pinfunction "2_2") (pintype "passive"))
    )
    (net (code "60") (name "Net-(D9-A)") (class "Default")
      (node (ref "D9") (pin "1") (pinfunction "A_1") (pintype "passive"))
      (node (ref "Q7") (pin "1") (pinfunction "D_1") (pintype "passive"))
      (node (ref "R21") (pin "1") (pinfunction "1_1") (pintype "passive"))
    )
    (net (code "61") (name "Net-(D9-K)") (class "Default")
      (node (ref "D9") (pin "2") (pinfunction "K_2") (pintype "passive"))
      (node (ref "R51") (pin "2") (pinfunction "2_2") (pintype "passive"))
    )
    (net (code "62") (name "Net-(P2-Pad10)") (class "Default")
      (node (ref "P2") (pin "10") (pinfunction "10_10") (pintype "passive"))
      (node (ref "R38") (pin "2") (pinfunction "2_2") (pintype "passive"))
    )
    (net (code "63") (name "Net-(P2-Pad11)") (class "Default")
      (node (ref "P2") (pin "11") (pinfunction "11_11") (pintype "passive"))
      (node (ref "R39") (pin "2") (pinfunction "2_2") (pintype "passive"))
    )
    (net (code "64") (name "Net-(P2-Pad12)") (class "Default")
      (node (ref "P2") (pin "12") (pinfunction "12_12") (pintype "passive"))
      (node (ref "R37") (pin "1") (pinfunction "1_1") (pintype "passive"))
    )
    (net (code "65") (name "Net-(P2-Pad13)") (class "Default")
      (node (ref "P2") (pin "13") (pinfunction "13_13") (pintype "passive"))
      (node (ref "R36") (pin "1") (pinfunction "1_1") (pintype "passive"))
    )
    (net (code "66") (name "Net-(Q1-G)") (class "Default")
      (node (ref "Q1") (pin "2") (pinfunction "G_2") (pintype "passive"))
      (node (ref "R2") (pin "1") (pinfunction "1_1") (pintype "passive"))
    )
    (net (code "67") (name "Net-(Q2-G)") (class "Default")
      (node (ref "Q2") (pin "2") (pinfunction "G_2") (pintype "passive"))
      (node (ref "R5") (pin "1") (pinfunction "1_1") (pintype "passive"))
    )
    (net (code "68") (name "Net-(Q3-G)") (class "Default")
      (node (ref "Q3") (pin "2") (pinfunction "G_2") (pintype "passive"))
      (node (ref "R8") (pin "1") (pinfunction "1_1") (pintype "passive"))
    )
    (net (code "69") (name "Net-(Q4-G)") (class "Default")
      (node (ref "Q4") (pin "2") (pinfunction "G_2") (pintype "passive"))
      (node (ref "R11") (pin "1") (pinfunction "1_1") (pintype "passive"))
    )
    (net (code "70") (name "Net-(Q5-G)") (class "Default")
      (node (ref "Q5") (pin "2") (pinfunction "G_2") (pintype "passive"))
      (node (ref "R14") (pin "1") (pinfunction "1_1") (pintype "passive"))
    )
    (net (code "71") (name "Net-(Q6-G)") (class "Default")
      (node (ref "Q6") (pin "2") (pinfunction "G_2") (pintype "passive"))
      (node (ref "R17") (pin "1") (pinfunction "1_1") (pintype "passive"))
    )
    (net (code "72") (name "Net-(Q7-G)") (class "Default")
      (node (ref "Q7") (pin "2") (pinfunction "G_2") (pintype "passive"))
      (node (ref "R20") (pin "1") (pinfunction "1_1") (pintype "passive"))
    )
    (net (code "73") (name "Net-(Q9-C)") (class "Default")
      (node (ref "C10") (pin "2") (pinfunction "2_2") (pintype "passive"))
      (node (ref "Q9") (pin "3") (pinfunction "C_3") (pintype "passive"))
      (node (ref "R25") (pin "1") (pinfunction "1_1") (pintype "passive"))
    )
    (net (code "74") (name "Net-(R28-Pad1)") (class "Default")
      (node (ref "R28") (pin "1") (pinfunction "1_1") (pintype "passive"))
      (node (ref "S1") (pin "1") (pinfunction "1_1") (pintype "passive"))
    )
    (net (code "75") (name "Net-(R29-Pad1)") (class "Default")
      (node (ref "R29") (pin "1") (pinfunction "1_1") (pintype "passive"))
      (node (ref "S3") (pin "1") (pinfunction "1_1") (pintype "passive"))
    )
    (net (code "76") (name "Net-(R34-Pad1)") (class "Default")
      (node (ref "R34") (pin "1") (pinfunction "1_1") (pintype "passive"))
      (node (ref "S1") (pin "3") (pinfunction "3_3") (pintype "passive"))
      (node (ref "XFMR") (pin "9") (pinfunction "9_9") (pintype "passive"))
    )
    (net (code "77") (name "Net-(R35-Pad2)") (class "Default")
      (node (ref "R35") (pin "2") (pinfunction "2_2") (pintype "passive"))
      (node (ref "S3") (pin "3") (pinfunction "3_3") (pintype "passive"))
      (node (ref "XFMR") (pin "10") (pinfunction "10_10") (pintype "passive"))
    )
    (net (code "78") (name "Net-(U1-C4)") (class "Default")
      (node (ref "R27") (pin "2") (pinfunction "2_2") (pintype "passive"))
      (node (ref "U1") (pin "28") (pinfunction "C5_28") (pintype "passive"))
      (node (ref "U1") (pin "30") (pinfunction "C4_30") (pintype "passive"))
    )
    (net (code "79") (name "Net-(U1-C10)") (class "Default")
      (node (ref "R26") (pin "2") (pinfunction "2_2") (pintype "passive"))
      (node (ref "U1") (pin "16") (pinfunction "C10_16") (pintype "passive"))
      (node (ref "U1") (pin "18") (pinfunction "C9_18") (pintype "passive"))
      (node (ref "U1") (pin "20") (pinfunction "C8_20") (pintype "passive"))
    )
    (net (code "80") (name "Net-(U1-C13)") (class "Default")
      (node (ref "R24") (pin "2") (pinfunction "2_2") (pintype "passive"))
      (node (ref "U1") (pin "4") (pinfunction "C15_4") (pintype "passive"))
      (node (ref "U1") (pin "6") (pinfunction "C14_6") (pintype "passive"))
      (node (ref "U1") (pin "8") (pinfunction "C13_8") (pintype "passive"))
    )
    (net (code "81") (name "Net-(U1-DTEN)") (class "Default")
      (node (ref "S4") (pin "2") (pinfunction "2_2") (pintype "passive"))
      (node (ref "U1") (pin "52") (pinfunction "DTEN_52") (pintype "passive"))
    )
    (net (code "82") (name "Net-(U1-IBIAS)") (class "Default")
      (node (ref "R30") (pin "1") (pinfunction "1_1") (pintype "passive"))
      (node (ref "U1") (pin "57") (pinfunction "IBIAS_57") (pintype "passive"))
    )
    (net (code "83") (name "Net-(U1-ICMP)") (class "Default")
      (node (ref "R30") (pin "2") (pinfunction "2_2") (pintype "passive"))
      (node (ref "R31") (pin "1") (pinfunction "1_1") (pintype "passive"))
      (node (ref "U1") (pin "58") (pinfunction "ICMP_58") (pintype "passive"))
    )
    (net (code "84") (name "Net-(U1-IMB)") (class "Default")
      (node (ref "R33") (pin "2") (pinfunction "2_2") (pintype "passive"))
      (node (ref "U1") (pin "63") (pinfunction "IMB_63") (pintype "passive"))
      (node (ref "XFMR") (pin "7") (pinfunction "7_7") (pintype "passive"))
    )
    (net (code "85") (name "Net-(U1-IPB)") (class "Default")
      (node (ref "R32") (pin "1") (pinfunction "1_1") (pintype "passive"))
      (node (ref "U1") (pin "64") (pinfunction "IPB_64") (pintype "passive"))
      (node (ref "XFMR") (pin "6") (pinfunction "6_6") (pintype "passive"))
    )
    (net (code "86") (name "Net-(U1-ISOMD)") (class "Default")
      (node (ref "S2") (pin "2") (pinfunction "2_2") (pintype "passive"))
      (node (ref "U1") (pin "55") (pinfunction "ISOMD_55") (pintype "passive"))
    )
    (net (code "87") (name "Net-(U1-V+)") (class "Default")
      (node (ref "C9") (pin "2") (pinfunction "2_2") (pintype "passive"))
      (node (ref "R22") (pin "1") (pinfunction "1_1") (pintype "passive"))
      (node (ref "U1") (pin "1") (pinfunction "V+_1") (pintype "passive"))
    )
    (net (code "88") (name "VCC") (class "Default")
      (node (ref "BT1") (pin "1") (pinfunction "+_1") (pintype "passive"))
      (node (ref "J5") (pin "1") (pinfunction "1_1") (pintype "passive"))
      (node (ref "P10") (pin "1") (pinfunction "1_1") (pintype "passive"))
      (node (ref "P10") (pin "2") (pinfunction "2_2") (pintype "passive"))
      (node (ref "P11") (pin "1") (pinfunction "1_1") (pintype "passive"))
      (node (ref "P11") (pin "2") (pinfunction "2_2") (pintype "passive"))
      (node (ref "P2") (pin "9") (pinfunction "9_9") (pintype "passive"))
      (node (ref "P6") (pin "1") (pinfunction "1_1") (pintype "passive"))
      (node (ref "P6") (pin "2") (pinfunction "2_2") (pintype "passive"))
      (node (ref "P7") (pin "1") (pinfunction "1_1") (pintype "passive"))
      (node (ref "P7") (pin "2") (pinfunction "2_2") (pintype "passive"))
      (node (ref "Q1") (pin "3") (pinfunction "S_3") (pintype "passive"))
      (node (ref "R1") (pin "1") (pinfunction "1_1") (pintype "passive"))
      (node (ref "R24") (pin "1") (pinfunction "1_1") (pintype "passive"))
      (node (ref "R25") (pin "2") (pinfunction "2_2") (pintype "passive"))
      (node (ref "R26") (pin "1") (pinfunction "1_1") (pintype "passive"))
      (node (ref "R27") (pin "1") (pinfunction "1_1") (pintype "passive"))
      (node (ref "S5") (pin "2") (pinfunction "2_2") (pintype "passive"))
    )
    (net (code "89") (name "unconnected-(P2-Pad14)") (class "Default")
      (node (ref "P2") (pin "14") (pinfunction "14_14") (pintype "passive+no_connect"))
    )
    (net (code "90") (name "unconnected-(S5-Pad1)") (class "Default")
      (node (ref "S5") (pin "1") (pinfunction "1_1") (pintype "passive+no_connect"))
    )
    (net (code "91") (name "unconnected-(U1-NC-Pad2)") (class "Default")
      (node (ref "U1") (pin "2") (pinfunction "NC_2") (pintype "passive+no_connect"))
    )
    (net (code "92") (name "unconnected-(U1-NC-Pad3)") (class "Default")
      (node (ref "U1") (pin "3") (pinfunction "NC_3") (pintype "passive+no_connect"))
    )
    (net (code "93") (name "unconnected-(U1-NC-Pad14)") (class "Default")
      (node (ref "U1") (pin "14") (pinfunction "NC_14") (pintype "passive+no_connect"))
    )
    (net (code "94") (name "unconnected-(U1-NC-Pad15)") (class "Default")
      (node (ref "U1") (pin "15") (pinfunction "NC_15") (pintype "passive+no_connect"))
    )
    (net (code "95") (name "unconnected-(U1-NC-Pad26)") (class "Default")
      (node (ref "U1") (pin "26") (pinfunction "NC_26") (pintype "passive+no_connect"))
    )
    (net (code "96") (name "unconnected-(U1-NC-Pad27)") (class "Default")
      (node (ref "U1") (pin "27") (pinfunction "NC_27") (pintype "passive+no_connect"))
    )
    (net (code "97") (name "unconnected-(U1-S4-Pad31)") (class "Default")
      (node (ref "U1") (pin "31") (pinfunction "S4_31") (pintype "passive+no_connect"))
    )
    (net (code "98") (name "unconnected-(U1-S5-Pad29)") (class "Default")
      (node (ref "U1") (pin "29") (pinfunction "S5_29") (pintype "passive+no_connect"))
    )
    (net (code "99") (name "unconnected-(U1-S8-Pad21)") (class "Default")
      (node (ref "U1") (pin "21") (pinfunction "S8_21") (pintype "passive"))
    )
    (net (code "100") (name "unconnected-(U1-S9-Pad19)") (class "Default")
      (node (ref "U1") (pin "19") (pinfunction "S9_19") (pintype "passive+no_connect"))
    )
    (net (code "101") (name "unconnected-(U1-S10-Pad17)") (class "Default")
      (node (ref "U1") (pin "17") (pinfunction "S10_17") (pintype "passive+no_connect"))
    )
    (net (code "102") (name "unconnected-(U1-S13-Pad9)") (class "Default")
      (node (ref "U1") (pin "9") (pinfunction "S13_9") (pintype "passive+no_connect"))
    )
    (net (code "103") (name "unconnected-(U1-S14-Pad7)") (class "Default")
      (node (ref "U1") (pin "7") (pinfunction "S14_7") (pintype "passive+no_connect"))
    )
    (net (code "104") (name "unconnected-(U1-S15-Pad5)") (class "Default")
      (node (ref "U1") (pin "5") (pinfunction "S15_5") (pintype "passive+no_connect"))
    )
    (net (code "105") (name "unconnected-(XFMR-Pad3)") (class "Default")
      (node (ref "XFMR") (pin "3") (pinfunction "3_3") (pintype "passive+no_connect"))
    )
    (net (code "106") (name "unconnected-(XFMR-Pad8)") (class "Default")
      (node (ref "XFMR") (pin "8") (pinfunction "8_8") (pintype "passive+no_connect"))
    )
  )
)
